# sensor_board.net
KiCad netlist of a schematic drawn in EAGLE
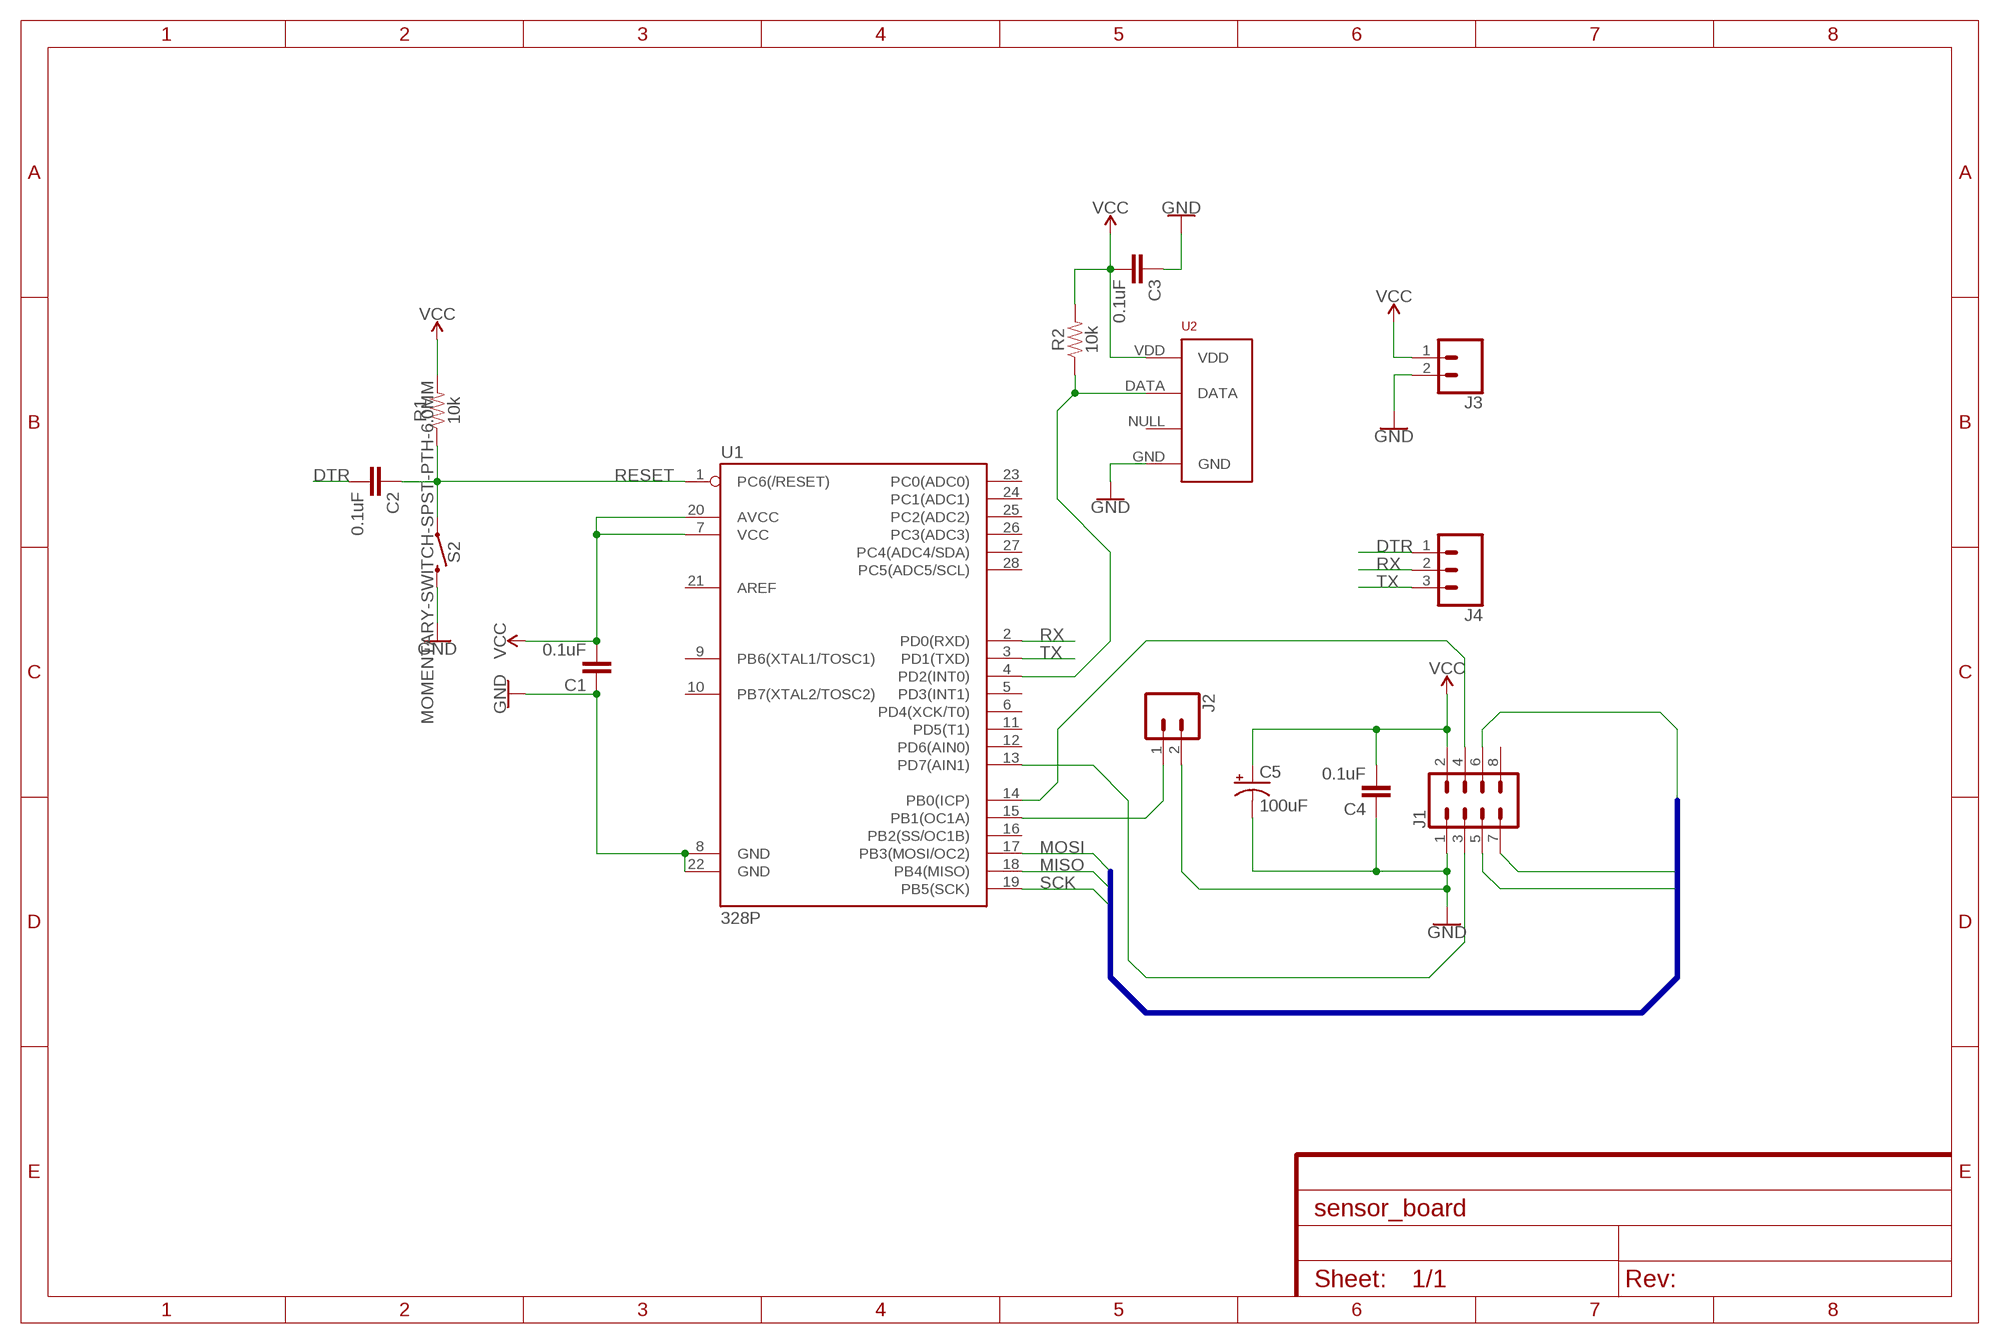
[diagram p0: schematic, sheet 1]

(export (version "E")
  (design (tool "Eeschema 10.0.6"))
  (components
    (comp (ref "C1")
      (value "0.1uF")
      (footprint "eagle-import:CAP-PTH-SMALL-KIT")
      (libsource (lib "eagle-import") (part "0.1UF-KIT-EZ-50V-20%"))
    )
    (comp (ref "C2")
      (value "0.1uF")
      (footprint "eagle-import:CAP-PTH-SMALL-KIT")
      (libsource (lib "eagle-import") (part "0.1UF-KIT-EZ-50V-20%"))
    )
    (comp (ref "C3")
      (value "0.1uF")
      (footprint "eagle-import:CAP-PTH-SMALL-KIT")
      (libsource (lib "eagle-import") (part "0.1UF-KIT-EZ-50V-20%"))
    )
    (comp (ref "C4")
      (value "0.1uF")
      (footprint "eagle-import:CAP-PTH-SMALL-KIT")
      (libsource (lib "eagle-import") (part "0.1UF-KIT-EZ-50V-20%"))
    )
    (comp (ref "C5")
      (value "100uF")
      (footprint "eagle-import:CPOL-RADIAL-2.5MM-6.5MM")
      (libsource (lib "eagle-import") (part "100UF-POLAR-RADIAL-2.5MM-25V-20%"))
    )
    (comp (ref "J1")
      (value "CONN_04X2")
      (footprint "eagle-import:2X4")
      (libsource (lib "eagle-import") (part "CONN_04X2"))
    )
    (comp (ref "J2")
      (value "CONN_02")
      (footprint "eagle-import:1X02")
      (libsource (lib "eagle-import") (part "CONN_02"))
    )
    (comp (ref "J3")
      (value "CONN_02")
      (footprint "eagle-import:1X02")
      (libsource (lib "eagle-import") (part "CONN_02"))
    )
    (comp (ref "J4")
      (value "CONN_03")
      (footprint "eagle-import:1X03")
      (libsource (lib "eagle-import") (part "CONN_03"))
    )
    (comp (ref "R1")
      (value "10k")
      (footprint "eagle-import:AXIAL-0.3")
      (libsource (lib "eagle-import") (part "10KOHM-HORIZ-1/4W-1%"))
    )
    (comp (ref "R2")
      (value "10k")
      (footprint "eagle-import:AXIAL-0.3")
      (libsource (lib "eagle-import") (part "10KOHM-HORIZ-1/4W-1%"))
    )
    (comp (ref "S2")
      (value "MOMENTARY-SWITCH-SPST-PTH-6.0MM")
      (footprint "eagle-import:TACTILE_SWITCH_PTH_6.0MM")
      (libsource (lib "eagle-import") (part "MOMENTARY-SWITCH-SPST-PTH-6.0MM"))
    )
    (comp (ref "U1")
      (value "328P")
      (footprint "eagle-import:DIP28")
      (libsource (lib "eagle-import") (part "ATMEGA328P_PDIP"))
    )
    (comp (ref "U2")
      (value "RHT03_DHT-22_AM2302RA")
      (footprint "eagle-import:RHT03_DHT-22_RA")
      (libsource (lib "eagle-import") (part "RHT03_DHT-22_AM2302RA"))
    )
  )
  (nets
    (net (code "1") (name "/DTR") (class "Default")
      (node (ref "C2") (pin "2") (pinfunction "2_2") (pintype "passive"))
      (node (ref "J4") (pin "1") (pinfunction "1_1") (pintype "passive"))
    )
    (net (code "2") (name "/MISO") (class "Default")
      (node (ref "J1") (pin "7") (pinfunction "7_7") (pintype "passive"))
      (node (ref "U1") (pin "18") (pinfunction "PB4(MISO)_18") (pintype "bidirectional"))
    )
    (net (code "3") (name "/MOSI") (class "Default")
      (node (ref "J1") (pin "6") (pinfunction "6_6") (pintype "passive"))
      (node (ref "U1") (pin "17") (pinfunction "PB3(MOSI/OC2)_17") (pintype "bidirectional"))
    )
    (net (code "4") (name "/RESET") (class "Default")
      (node (ref "C2") (pin "1") (pinfunction "1_1") (pintype "passive"))
      (node (ref "R1") (pin "P$1") (pinfunction "1_P$1") (pintype "passive"))
      (node (ref "S2") (pin "1") (pinfunction "1_1") (pintype "passive"))
      (node (ref "U1") (pin "1") (pinfunction "PC6(/RESET)_1") (pintype "bidirectional"))
    )
    (net (code "5") (name "/RX") (class "Default")
      (node (ref "J4") (pin "2") (pinfunction "2_2") (pintype "passive"))
      (node (ref "U1") (pin "2") (pinfunction "PD0(RXD)_2") (pintype "bidirectional"))
    )
    (net (code "6") (name "/SCK") (class "Default")
      (node (ref "J1") (pin "5") (pinfunction "5_5") (pintype "passive"))
      (node (ref "U1") (pin "19") (pinfunction "PB5(SCK)_19") (pintype "bidirectional"))
    )
    (net (code "7") (name "/TX") (class "Default")
      (node (ref "J4") (pin "3") (pinfunction "3_3") (pintype "passive"))
      (node (ref "U1") (pin "3") (pinfunction "PD1(TXD)_3") (pintype "bidirectional"))
    )
    (net (code "8") (name "GND") (class "Default")
      (node (ref "C1") (pin "1") (pinfunction "1_1") (pintype "passive"))
      (node (ref "C3") (pin "1") (pinfunction "1_1") (pintype "passive"))
      (node (ref "C4") (pin "1") (pinfunction "1_1") (pintype "passive"))
      (node (ref "C5") (pin "2") (pinfunction "-_2") (pintype "passive"))
      (node (ref "J1") (pin "1") (pinfunction "1_1") (pintype "passive"))
      (node (ref "J2") (pin "2") (pinfunction "2_2") (pintype "passive"))
      (node (ref "J3") (pin "2") (pinfunction "2_2") (pintype "passive"))
      (node (ref "S2") (pin "3") (pinfunction "2_3") (pintype "passive"))
      (node (ref "U1") (pin "22") (pinfunction "GND_22") (pintype "bidirectional"))
      (node (ref "U1") (pin "8") (pinfunction "GND_8") (pintype "bidirectional"))
      (node (ref "U2") (pin "GND") (pinfunction "GND_GND") (pintype "power_in"))
    )
    (net (code "9") (name "Net-(R2-1)") (class "Default")
      (node (ref "R2") (pin "P$1") (pinfunction "1_P$1") (pintype "passive"))
      (node (ref "U1") (pin "4") (pinfunction "PD2(INT0)_4") (pintype "bidirectional"))
      (node (ref "U2") (pin "DATA") (pinfunction "DATA_DATA") (pintype "bidirectional"))
    )
    (net (code "10") (name "Net-(U1-PB0(ICP))") (class "Default")
      (node (ref "J1") (pin "4") (pinfunction "4_4") (pintype "passive"))
      (node (ref "U1") (pin "14") (pinfunction "PB0(ICP)_14") (pintype "bidirectional"))
    )
    (net (code "11") (name "Net-(U1-PB1(OC1A))") (class "Default")
      (node (ref "J2") (pin "1") (pinfunction "1_1") (pintype "passive"))
      (node (ref "U1") (pin "15") (pinfunction "PB1(OC1A)_15") (pintype "bidirectional"))
    )
    (net (code "12") (name "Net-(U1-PD7(AIN1))") (class "Default")
      (node (ref "J1") (pin "3") (pinfunction "3_3") (pintype "passive"))
      (node (ref "U1") (pin "13") (pinfunction "PD7(AIN1)_13") (pintype "bidirectional"))
    )
    (net (code "13") (name "VCC") (class "Default")
      (node (ref "C1") (pin "2") (pinfunction "2_2") (pintype "passive"))
      (node (ref "C3") (pin "2") (pinfunction "2_2") (pintype "passive"))
      (node (ref "C4") (pin "2") (pinfunction "2_2") (pintype "passive"))
      (node (ref "C5") (pin "1") (pinfunction "+_1") (pintype "passive"))
      (node (ref "J1") (pin "2") (pinfunction "2_2") (pintype "passive"))
      (node (ref "J3") (pin "1") (pinfunction "1_1") (pintype "passive"))
      (node (ref "R1") (pin "P$2") (pinfunction "2_P$2") (pintype "passive"))
      (node (ref "R2") (pin "P$2") (pinfunction "2_P$2") (pintype "passive"))
      (node (ref "U1") (pin "20") (pinfunction "AVCC_20") (pintype "bidirectional"))
      (node (ref "U1") (pin "7") (pinfunction "VCC_7") (pintype "bidirectional"))
      (node (ref "U2") (pin "VDD") (pinfunction "VDD_VDD") (pintype "power_in"))
    )
    (net (code "14") (name "unconnected-(J1-Pad8)") (class "Default")
      (node (ref "J1") (pin "8") (pinfunction "8_8") (pintype "passive"))
    )
    (net (code "15") (name "unconnected-(U1-AREF-Pad21)") (class "Default")
      (node (ref "U1") (pin "21") (pinfunction "AREF_21") (pintype "bidirectional"))
    )
    (net (code "16") (name "unconnected-(U1-PB2(SS{slash}OC1B)-Pad16)") (class "Default")
      (node (ref "U1") (pin "16") (pinfunction "PB2(SS/OC1B)_16") (pintype "bidirectional"))
    )
    (net (code "17") (name "unconnected-(U1-PB6(XTAL1{slash}TOSC1)-Pad9)") (class "Default")
      (node (ref "U1") (pin "9") (pinfunction "PB6(XTAL1/TOSC1)_9") (pintype "bidirectional"))
    )
    (net (code "18") (name "unconnected-(U1-PB7(XTAL2{slash}TOSC2)-Pad10)") (class "Default")
      (node (ref "U1") (pin "10") (pinfunction "PB7(XTAL2/TOSC2)_10") (pintype "bidirectional"))
    )
    (net (code "19") (name "unconnected-(U1-PC0(ADC0)-Pad23)") (class "Default")
      (node (ref "U1") (pin "23") (pinfunction "PC0(ADC0)_23") (pintype "bidirectional"))
    )
    (net (code "20") (name "unconnected-(U1-PC1(ADC1)-Pad24)") (class "Default")
      (node (ref "U1") (pin "24") (pinfunction "PC1(ADC1)_24") (pintype "bidirectional"))
    )
    (net (code "21") (name "unconnected-(U1-PC2(ADC2)-Pad25)") (class "Default")
      (node (ref "U1") (pin "25") (pinfunction "PC2(ADC2)_25") (pintype "bidirectional"))
    )
    (net (code "22") (name "unconnected-(U1-PC3(ADC3)-Pad26)") (class "Default")
      (node (ref "U1") (pin "26") (pinfunction "PC3(ADC3)_26") (pintype "bidirectional"))
    )
    (net (code "23") (name "unconnected-(U1-PC4(ADC4{slash}SDA)-Pad27)") (class "Default")
      (node (ref "U1") (pin "27") (pinfunction "PC4(ADC4/SDA)_27") (pintype "bidirectional"))
    )
    (net (code "24") (name "unconnected-(U1-PC5(ADC5{slash}SCL)-Pad28)") (class "Default")
      (node (ref "U1") (pin "28") (pinfunction "PC5(ADC5/SCL)_28") (pintype "bidirectional"))
    )
    (net (code "25") (name "unconnected-(U1-PD3(INT1)-Pad5)") (class "Default")
      (node (ref "U1") (pin "5") (pinfunction "PD3(INT1)_5") (pintype "bidirectional"))
    )
    (net (code "26") (name "unconnected-(U1-PD4(XCK{slash}T0)-Pad6)") (class "Default")
      (node (ref "U1") (pin "6") (pinfunction "PD4(XCK/T0)_6") (pintype "bidirectional"))
    )
    (net (code "27") (name "unconnected-(U1-PD5(T1)-Pad11)") (class "Default")
      (node (ref "U1") (pin "11") (pinfunction "PD5(T1)_11") (pintype "bidirectional"))
    )
    (net (code "28") (name "unconnected-(U1-PD6(AIN0)-Pad12)") (class "Default")
      (node (ref "U1") (pin "12") (pinfunction "PD6(AIN0)_12") (pintype "bidirectional"))
    )
    (net (code "29") (name "unconnected-(U2-PadNULL)") (class "Default")
      (node (ref "U2") (pin "NULL") (pinfunction "NULL_NULL") (pintype "no_connect"))
    )
  )
)
